# sub_sys_pdu.net
KiCad netlist of a schematic drawn in EAGLE
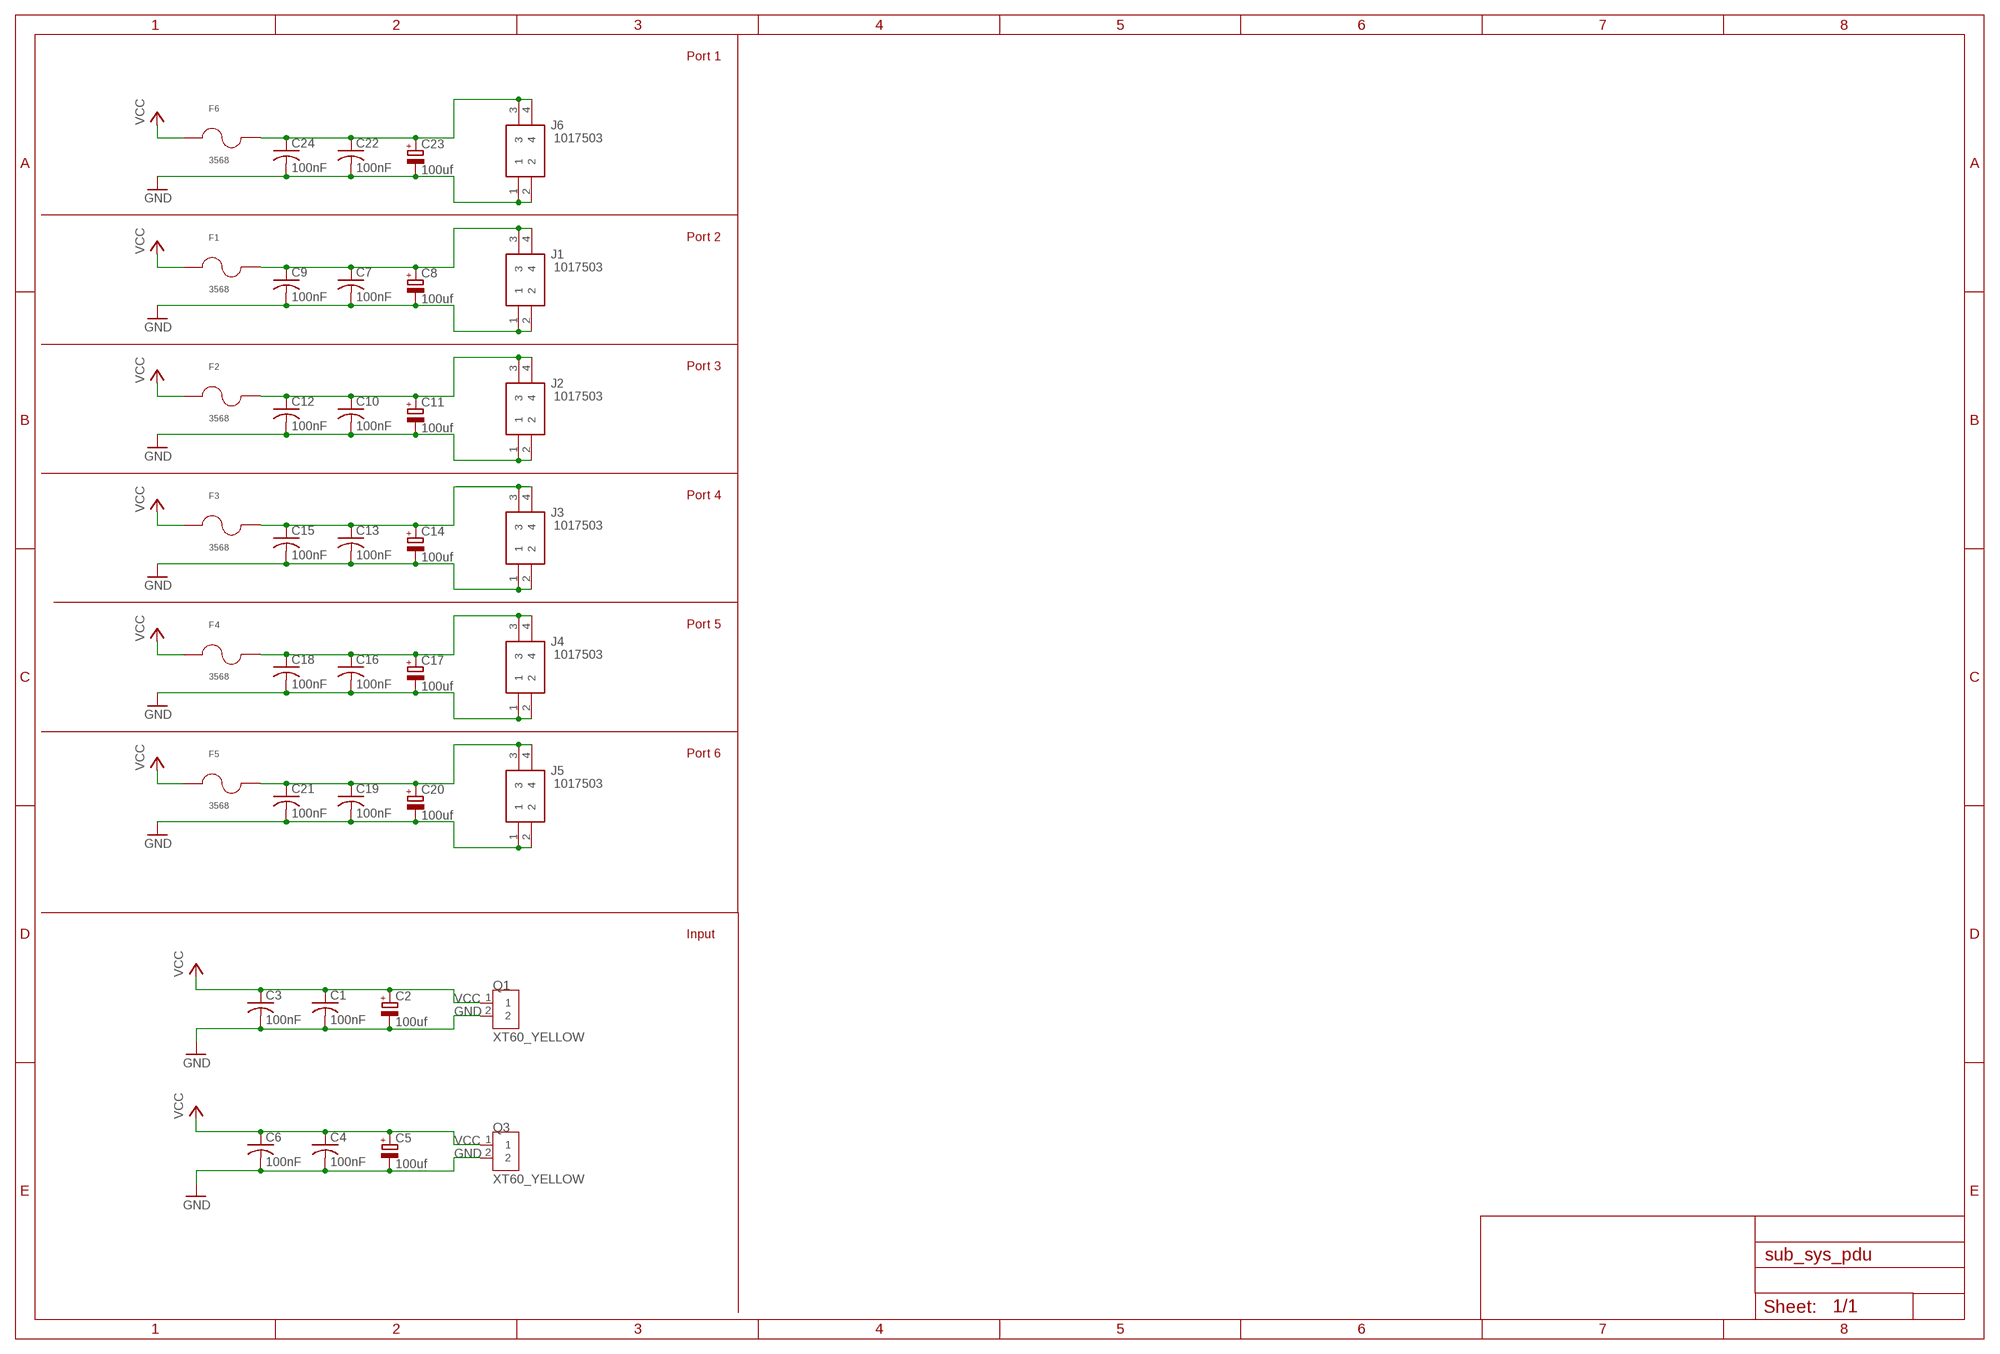
[diagram p0: schematic, sheet 1]

(export (version "E")
  (design (tool "Eeschema 10.0.6"))
  (components
    (comp (ref "C1")
      (value "100nF")
      (footprint "eagle-import:C0805")
      (libsource (lib "eagle-import") (part "C-USC0805"))
    )
    (comp (ref "C2")
      (value "100uf")
      (footprint "eagle-import:E5-10,5")
      (libsource (lib "eagle-import") (part "CPOL-EUE5-10.5"))
    )
    (comp (ref "C3")
      (value "100nF")
      (footprint "eagle-import:C0805")
      (libsource (lib "eagle-import") (part "C-USC0805"))
    )
    (comp (ref "C4")
      (value "100nF")
      (footprint "eagle-import:C0805")
      (libsource (lib "eagle-import") (part "C-USC0805"))
    )
    (comp (ref "C5")
      (value "100uf")
      (footprint "eagle-import:E5-10,5")
      (libsource (lib "eagle-import") (part "CPOL-EUE5-10.5"))
    )
    (comp (ref "C6")
      (value "100nF")
      (footprint "eagle-import:C0805")
      (libsource (lib "eagle-import") (part "C-USC0805"))
    )
    (comp (ref "C7")
      (value "100nF")
      (footprint "eagle-import:C0805")
      (libsource (lib "eagle-import") (part "C-USC0805"))
    )
    (comp (ref "C8")
      (value "100uf")
      (footprint "eagle-import:E5-10,5")
      (libsource (lib "eagle-import") (part "CPOL-EUE5-10.5"))
    )
    (comp (ref "C9")
      (value "100nF")
      (footprint "eagle-import:C0805")
      (libsource (lib "eagle-import") (part "C-USC0805"))
    )
    (comp (ref "C10")
      (value "100nF")
      (footprint "eagle-import:C0805")
      (libsource (lib "eagle-import") (part "C-USC0805"))
    )
    (comp (ref "C11")
      (value "100uf")
      (footprint "eagle-import:E5-10,5")
      (libsource (lib "eagle-import") (part "CPOL-EUE5-10.5"))
    )
    (comp (ref "C12")
      (value "100nF")
      (footprint "eagle-import:C0805")
      (libsource (lib "eagle-import") (part "C-USC0805"))
    )
    (comp (ref "C13")
      (value "100nF")
      (footprint "eagle-import:C0805")
      (libsource (lib "eagle-import") (part "C-USC0805"))
    )
    (comp (ref "C14")
      (value "100uf")
      (footprint "eagle-import:E5-10,5")
      (libsource (lib "eagle-import") (part "CPOL-EUE5-10.5"))
    )
    (comp (ref "C15")
      (value "100nF")
      (footprint "eagle-import:C0805")
      (libsource (lib "eagle-import") (part "C-USC0805"))
    )
    (comp (ref "C16")
      (value "100nF")
      (footprint "eagle-import:C0805")
      (libsource (lib "eagle-import") (part "C-USC0805"))
    )
    (comp (ref "C17")
      (value "100uf")
      (footprint "eagle-import:E5-10,5")
      (libsource (lib "eagle-import") (part "CPOL-EUE5-10.5"))
    )
    (comp (ref "C18")
      (value "100nF")
      (footprint "eagle-import:C0805")
      (libsource (lib "eagle-import") (part "C-USC0805"))
    )
    (comp (ref "C19")
      (value "100nF")
      (footprint "eagle-import:C0805")
      (libsource (lib "eagle-import") (part "C-USC0805"))
    )
    (comp (ref "C20")
      (value "100uf")
      (footprint "eagle-import:E5-10,5")
      (libsource (lib "eagle-import") (part "CPOL-EUE5-10.5"))
    )
    (comp (ref "C21")
      (value "100nF")
      (footprint "eagle-import:C0805")
      (libsource (lib "eagle-import") (part "C-USC0805"))
    )
    (comp (ref "C22")
      (value "100nF")
      (footprint "eagle-import:C0805")
      (libsource (lib "eagle-import") (part "C-USC0805"))
    )
    (comp (ref "C23")
      (value "100uf")
      (footprint "eagle-import:E5-10,5")
      (libsource (lib "eagle-import") (part "CPOL-EUE5-10.5"))
    )
    (comp (ref "C24")
      (value "100nF")
      (footprint "eagle-import:C0805")
      (libsource (lib "eagle-import") (part "C-USC0805"))
    )
    (comp (ref "F1")
      (value "3568")
      (footprint "eagle-import:FUSE_3568")
      (fields (field (name "MF") "Adafruit Industries"))
      (libsource (lib "eagle-import") (part "3568"))
    )
    (comp (ref "F2")
      (value "3568")
      (footprint "eagle-import:FUSE_3568")
      (fields (field (name "MF") "Adafruit Industries"))
      (libsource (lib "eagle-import") (part "3568"))
    )
    (comp (ref "F3")
      (value "3568")
      (footprint "eagle-import:FUSE_3568")
      (fields (field (name "MF") "Adafruit Industries"))
      (libsource (lib "eagle-import") (part "3568"))
    )
    (comp (ref "F4")
      (value "3568")
      (footprint "eagle-import:FUSE_3568")
      (fields (field (name "MF") "Adafruit Industries"))
      (libsource (lib "eagle-import") (part "3568"))
    )
    (comp (ref "F5")
      (value "3568")
      (footprint "eagle-import:FUSE_3568")
      (fields (field (name "MF") "Adafruit Industries"))
      (libsource (lib "eagle-import") (part "3568"))
    )
    (comp (ref "F6")
      (value "3568")
      (footprint "eagle-import:FUSE_3568")
      (fields (field (name "MF") "Adafruit Industries"))
      (libsource (lib "eagle-import") (part "3568"))
    )
    (comp (ref "J1")
      (value "1017503")
      (footprint "eagle-import:1017503")
      (fields (field (name "MOUSER_PART_NUMBER") "651-1017503"))
      (libsource (lib "eagle-import") (part "1017503"))
    )
    (comp (ref "J2")
      (value "1017503")
      (footprint "eagle-import:1017503")
      (fields (field (name "MOUSER_PART_NUMBER") "651-1017503"))
      (libsource (lib "eagle-import") (part "1017503"))
    )
    (comp (ref "J3")
      (value "1017503")
      (footprint "eagle-import:1017503")
      (fields (field (name "MOUSER_PART_NUMBER") "651-1017503"))
      (libsource (lib "eagle-import") (part "1017503"))
    )
    (comp (ref "J4")
      (value "1017503")
      (footprint "eagle-import:1017503")
      (fields (field (name "MOUSER_PART_NUMBER") "651-1017503"))
      (libsource (lib "eagle-import") (part "1017503"))
    )
    (comp (ref "J5")
      (value "1017503")
      (footprint "eagle-import:1017503")
      (fields (field (name "MOUSER_PART_NUMBER") "651-1017503"))
      (libsource (lib "eagle-import") (part "1017503"))
    )
    (comp (ref "J6")
      (value "1017503")
      (footprint "eagle-import:1017503")
      (fields (field (name "MOUSER_PART_NUMBER") "651-1017503"))
      (libsource (lib "eagle-import") (part "1017503"))
    )
    (comp (ref "Q1")
      (value "XT60_YELLOW")
      (footprint "eagle-import:AMASS_XT60PB-M")
      (fields (field (name "MF") "Pololu") (field (name "MP") "XT60 YELLOW"))
      (libsource (lib "eagle-import") (part "XT60_YELLOW"))
    )
    (comp (ref "Q3")
      (value "XT60_YELLOW")
      (footprint "eagle-import:AMASS_XT60PB-M")
      (fields (field (name "MF") "Pololu") (field (name "MP") "XT60 YELLOW"))
      (libsource (lib "eagle-import") (part "XT60_YELLOW"))
    )
  )
  (nets
    (net (code "1") (name "GND") (class "Default")
      (node (ref "C1") (pin "2") (pinfunction "2_2") (pintype "passive"))
      (node (ref "C10") (pin "2") (pinfunction "2_2") (pintype "passive"))
      (node (ref "C11") (pin "-") (pinfunction "-_-") (pintype "passive"))
      (node (ref "C12") (pin "2") (pinfunction "2_2") (pintype "passive"))
      (node (ref "C13") (pin "2") (pinfunction "2_2") (pintype "passive"))
      (node (ref "C14") (pin "-") (pinfunction "-_-") (pintype "passive"))
      (node (ref "C15") (pin "2") (pinfunction "2_2") (pintype "passive"))
      (node (ref "C16") (pin "2") (pinfunction "2_2") (pintype "passive"))
      (node (ref "C17") (pin "-") (pinfunction "-_-") (pintype "passive"))
      (node (ref "C18") (pin "2") (pinfunction "2_2") (pintype "passive"))
      (node (ref "C19") (pin "2") (pinfunction "2_2") (pintype "passive"))
      (node (ref "C2") (pin "-") (pinfunction "-_-") (pintype "passive"))
      (node (ref "C20") (pin "-") (pinfunction "-_-") (pintype "passive"))
      (node (ref "C21") (pin "2") (pinfunction "2_2") (pintype "passive"))
      (node (ref "C22") (pin "2") (pinfunction "2_2") (pintype "passive"))
      (node (ref "C23") (pin "-") (pinfunction "-_-") (pintype "passive"))
      (node (ref "C24") (pin "2") (pinfunction "2_2") (pintype "passive"))
      (node (ref "C3") (pin "2") (pinfunction "2_2") (pintype "passive"))
      (node (ref "C4") (pin "2") (pinfunction "2_2") (pintype "passive"))
      (node (ref "C5") (pin "-") (pinfunction "-_-") (pintype "passive"))
      (node (ref "C6") (pin "2") (pinfunction "2_2") (pintype "passive"))
      (node (ref "C7") (pin "2") (pinfunction "2_2") (pintype "passive"))
      (node (ref "C8") (pin "-") (pinfunction "-_-") (pintype "passive"))
      (node (ref "C9") (pin "2") (pinfunction "2_2") (pintype "passive"))
      (node (ref "J1") (pin "1") (pinfunction "1_1") (pintype "bidirectional"))
      (node (ref "J1") (pin "2") (pinfunction "2_2") (pintype "bidirectional"))
      (node (ref "J2") (pin "1") (pinfunction "1_1") (pintype "bidirectional"))
      (node (ref "J2") (pin "2") (pinfunction "2_2") (pintype "bidirectional"))
      (node (ref "J3") (pin "1") (pinfunction "1_1") (pintype "bidirectional"))
      (node (ref "J3") (pin "2") (pinfunction "2_2") (pintype "bidirectional"))
      (node (ref "J4") (pin "1") (pinfunction "1_1") (pintype "bidirectional"))
      (node (ref "J4") (pin "2") (pinfunction "2_2") (pintype "bidirectional"))
      (node (ref "J5") (pin "1") (pinfunction "1_1") (pintype "bidirectional"))
      (node (ref "J5") (pin "2") (pinfunction "2_2") (pintype "bidirectional"))
      (node (ref "J6") (pin "1") (pinfunction "1_1") (pintype "bidirectional"))
      (node (ref "J6") (pin "2") (pinfunction "2_2") (pintype "bidirectional"))
      (node (ref "Q1") (pin "2") (pinfunction "2_2") (pintype "passive"))
      (node (ref "Q3") (pin "2") (pinfunction "2_2") (pintype "passive"))
    )
    (net (code "2") (name "Net-(C7-Pad1)") (class "Default")
      (node (ref "C7") (pin "1") (pinfunction "1_1") (pintype "passive"))
      (node (ref "C8") (pin "+") (pinfunction "+_+") (pintype "passive"))
      (node (ref "C9") (pin "1") (pinfunction "1_1") (pintype "passive"))
      (node (ref "F1") (pin "2") (pinfunction "2_2") (pintype "passive"))
      (node (ref "F1") (pin "4") (pinfunction "2_4") (pintype "passive"))
      (node (ref "J1") (pin "3") (pinfunction "3_3") (pintype "bidirectional"))
      (node (ref "J1") (pin "4") (pinfunction "4_4") (pintype "bidirectional"))
    )
    (net (code "3") (name "Net-(C10-Pad1)") (class "Default")
      (node (ref "C10") (pin "1") (pinfunction "1_1") (pintype "passive"))
      (node (ref "C11") (pin "+") (pinfunction "+_+") (pintype "passive"))
      (node (ref "C12") (pin "1") (pinfunction "1_1") (pintype "passive"))
      (node (ref "F2") (pin "2") (pinfunction "2_2") (pintype "passive"))
      (node (ref "F2") (pin "4") (pinfunction "2_4") (pintype "passive"))
      (node (ref "J2") (pin "3") (pinfunction "3_3") (pintype "bidirectional"))
      (node (ref "J2") (pin "4") (pinfunction "4_4") (pintype "bidirectional"))
    )
    (net (code "4") (name "Net-(C13-Pad1)") (class "Default")
      (node (ref "C13") (pin "1") (pinfunction "1_1") (pintype "passive"))
      (node (ref "C14") (pin "+") (pinfunction "+_+") (pintype "passive"))
      (node (ref "C15") (pin "1") (pinfunction "1_1") (pintype "passive"))
      (node (ref "F3") (pin "2") (pinfunction "2_2") (pintype "passive"))
      (node (ref "F3") (pin "4") (pinfunction "2_4") (pintype "passive"))
      (node (ref "J3") (pin "3") (pinfunction "3_3") (pintype "bidirectional"))
      (node (ref "J3") (pin "4") (pinfunction "4_4") (pintype "bidirectional"))
    )
    (net (code "5") (name "Net-(C16-Pad1)") (class "Default")
      (node (ref "C16") (pin "1") (pinfunction "1_1") (pintype "passive"))
      (node (ref "C17") (pin "+") (pinfunction "+_+") (pintype "passive"))
      (node (ref "C18") (pin "1") (pinfunction "1_1") (pintype "passive"))
      (node (ref "F4") (pin "2") (pinfunction "2_2") (pintype "passive"))
      (node (ref "F4") (pin "4") (pinfunction "2_4") (pintype "passive"))
      (node (ref "J4") (pin "3") (pinfunction "3_3") (pintype "bidirectional"))
      (node (ref "J4") (pin "4") (pinfunction "4_4") (pintype "bidirectional"))
    )
    (net (code "6") (name "Net-(C19-Pad1)") (class "Default")
      (node (ref "C19") (pin "1") (pinfunction "1_1") (pintype "passive"))
      (node (ref "C20") (pin "+") (pinfunction "+_+") (pintype "passive"))
      (node (ref "C21") (pin "1") (pinfunction "1_1") (pintype "passive"))
      (node (ref "F5") (pin "2") (pinfunction "2_2") (pintype "passive"))
      (node (ref "F5") (pin "4") (pinfunction "2_4") (pintype "passive"))
      (node (ref "J5") (pin "3") (pinfunction "3_3") (pintype "bidirectional"))
      (node (ref "J5") (pin "4") (pinfunction "4_4") (pintype "bidirectional"))
    )
    (net (code "7") (name "Net-(C22-Pad1)") (class "Default")
      (node (ref "C22") (pin "1") (pinfunction "1_1") (pintype "passive"))
      (node (ref "C23") (pin "+") (pinfunction "+_+") (pintype "passive"))
      (node (ref "C24") (pin "1") (pinfunction "1_1") (pintype "passive"))
      (node (ref "F6") (pin "2") (pinfunction "2_2") (pintype "passive"))
      (node (ref "F6") (pin "4") (pinfunction "2_4") (pintype "passive"))
      (node (ref "J6") (pin "3") (pinfunction "3_3") (pintype "bidirectional"))
      (node (ref "J6") (pin "4") (pinfunction "4_4") (pintype "bidirectional"))
    )
    (net (code "8") (name "VCC") (class "Default")
      (node (ref "C1") (pin "1") (pinfunction "1_1") (pintype "passive"))
      (node (ref "C2") (pin "+") (pinfunction "+_+") (pintype "passive"))
      (node (ref "C3") (pin "1") (pinfunction "1_1") (pintype "passive"))
      (node (ref "C4") (pin "1") (pinfunction "1_1") (pintype "passive"))
      (node (ref "C5") (pin "+") (pinfunction "+_+") (pintype "passive"))
      (node (ref "C6") (pin "1") (pinfunction "1_1") (pintype "passive"))
      (node (ref "F1") (pin "1") (pinfunction "1_1") (pintype "passive"))
      (node (ref "F1") (pin "3") (pinfunction "1_3") (pintype "passive"))
      (node (ref "F2") (pin "1") (pinfunction "1_1") (pintype "passive"))
      (node (ref "F2") (pin "3") (pinfunction "1_3") (pintype "passive"))
      (node (ref "F3") (pin "1") (pinfunction "1_1") (pintype "passive"))
      (node (ref "F3") (pin "3") (pinfunction "1_3") (pintype "passive"))
      (node (ref "F4") (pin "1") (pinfunction "1_1") (pintype "passive"))
      (node (ref "F4") (pin "3") (pinfunction "1_3") (pintype "passive"))
      (node (ref "F5") (pin "1") (pinfunction "1_1") (pintype "passive"))
      (node (ref "F5") (pin "3") (pinfunction "1_3") (pintype "passive"))
      (node (ref "F6") (pin "1") (pinfunction "1_1") (pintype "passive"))
      (node (ref "F6") (pin "3") (pinfunction "1_3") (pintype "passive"))
      (node (ref "Q1") (pin "1") (pinfunction "1_1") (pintype "passive"))
      (node (ref "Q3") (pin "1") (pinfunction "1_1") (pintype "passive"))
    )
  )
)
